# Defectoscope.net
KiCad netlist of a schematic drawn in Altium Designer
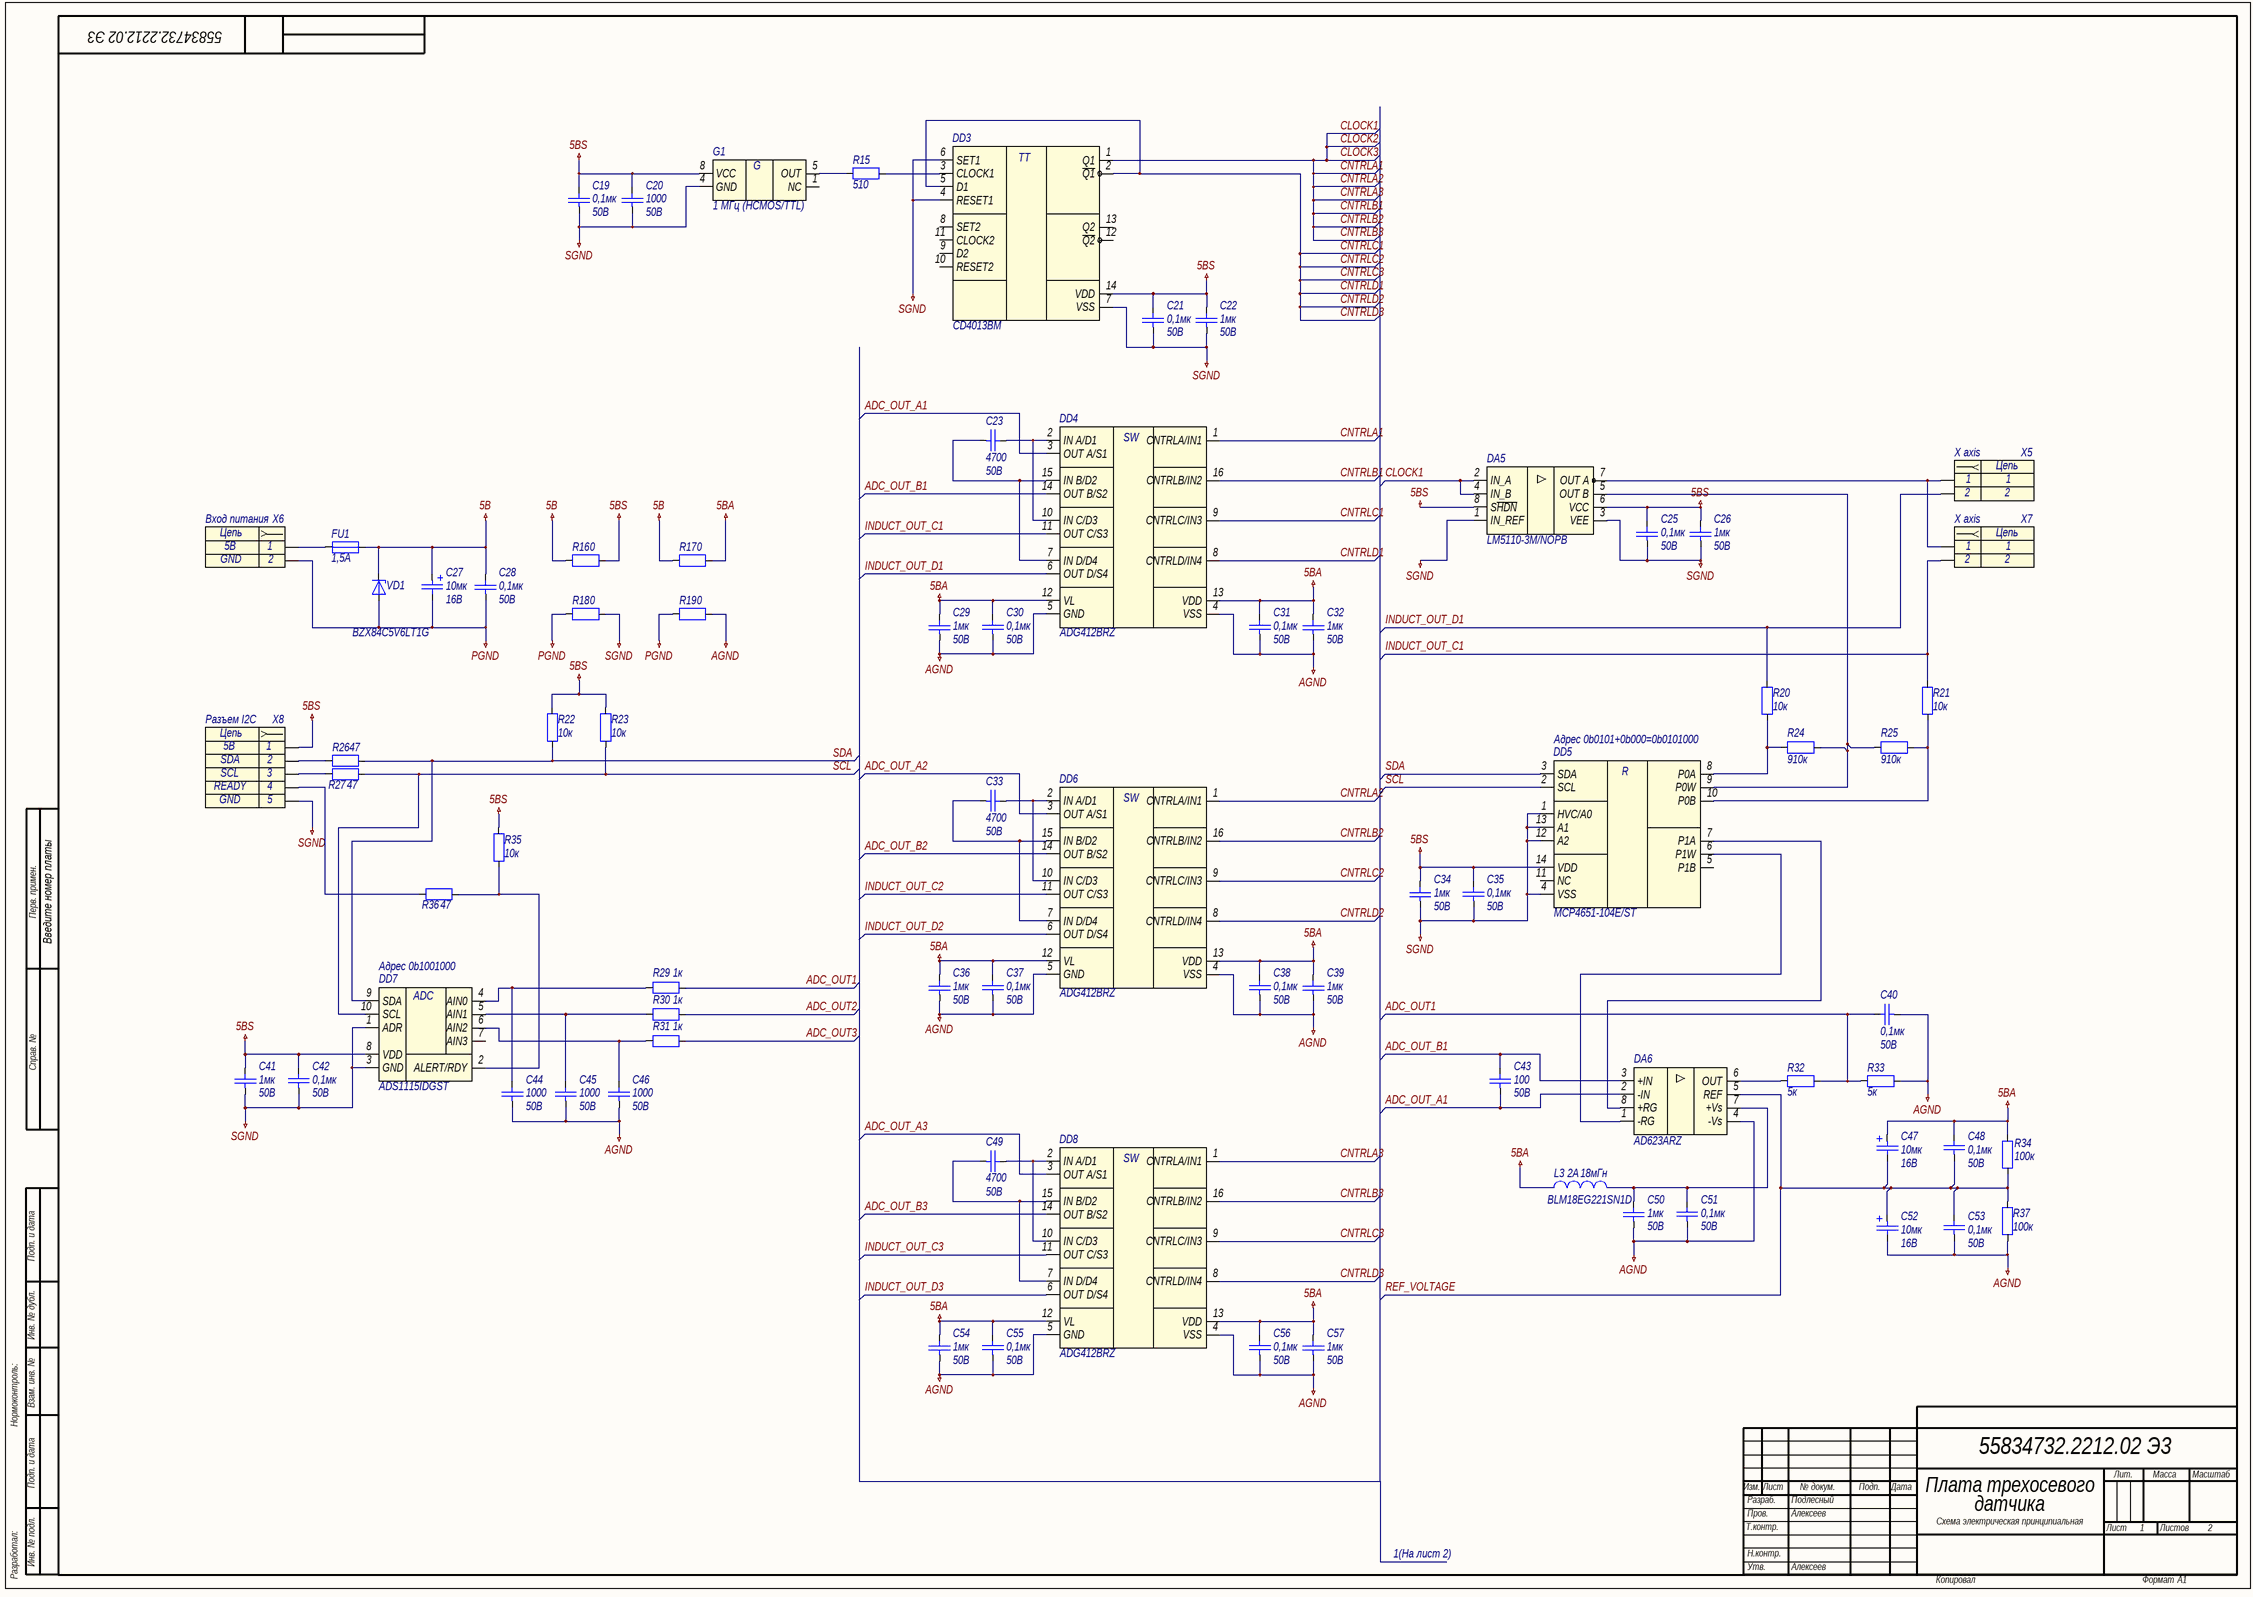
[diagram p0: Defectoscope.SchDoc]

(export (version "E")
  (design (tool "Eeschema 10.0.6"))
  (components
    (comp (ref "C19")
      (value "0,1мк")
      (footprint "ZabugorLib:C0805")
      (description "Конденсатор")
      (fields (field (name "VOLTAGE") "50В"))
      (libsource (lib "ZabugorLib") (part "Capacitor"))
    )
    (comp (ref "C20")
      (value "1000")
      (footprint "ZabugorLib:C0805")
      (description "Конденсатор")
      (fields (field (name "VOLTAGE") "50В"))
      (libsource (lib "ZabugorLib") (part "Capacitor"))
    )
    (comp (ref "C21")
      (value "0,1мк")
      (footprint "ZabugorLib:C0805")
      (description "Конденсатор")
      (fields (field (name "VOLTAGE") "50В"))
      (libsource (lib "ZabugorLib") (part "Capacitor"))
    )
    (comp (ref "C22")
      (value "1мк")
      (footprint "ZabugorLib:C0805")
      (description "Конденсатор")
      (fields (field (name "VOLTAGE") "50В"))
      (libsource (lib "ZabugorLib") (part "Capacitor"))
    )
    (comp (ref "C23")
      (value "4700")
      (footprint "ZabugorLib:C0805")
      (description "Конденсатор")
      (fields (field (name "VOLTAGE") "50В"))
      (libsource (lib "ZabugorLib") (part "Capacitor"))
    )
    (comp (ref "C25")
      (value "0,1мк")
      (footprint "ZabugorLib:C0805")
      (description "Конденсатор")
      (fields (field (name "VOLTAGE") "50В"))
      (libsource (lib "ZabugorLib") (part "Capacitor"))
    )
    (comp (ref "C26")
      (value "1мк")
      (footprint "ZabugorLib:C0805")
      (description "Конденсатор")
      (fields (field (name "VOLTAGE") "50В"))
      (libsource (lib "ZabugorLib") (part "Capacitor"))
    )
    (comp (ref "C27")
      (value "10мк")
      (footprint "ZabugorLib:TANTAL CASE B")
      (description "Конденсатор полярный")
      (fields (field (name "VOLTAGE") "16В"))
      (libsource (lib "ZabugorLib") (part "Capacitor_pol"))
    )
    (comp (ref "C28")
      (value "0,1мк")
      (footprint "ZabugorLib:C0805")
      (description "Конденсатор")
      (fields (field (name "VOLTAGE") "50В"))
      (libsource (lib "ZabugorLib") (part "Capacitor"))
    )
    (comp (ref "C29")
      (value "1мк")
      (footprint "ZabugorLib:C0805")
      (description "Конденсатор")
      (fields (field (name "VOLTAGE") "50В"))
      (libsource (lib "ZabugorLib") (part "Capacitor"))
    )
    (comp (ref "C30")
      (value "0,1мк")
      (footprint "ZabugorLib:C0805")
      (description "Конденсатор")
      (fields (field (name "VOLTAGE") "50В"))
      (libsource (lib "ZabugorLib") (part "Capacitor"))
    )
    (comp (ref "C31")
      (value "0,1мк")
      (footprint "ZabugorLib:C0805")
      (description "Конденсатор")
      (fields (field (name "VOLTAGE") "50В"))
      (libsource (lib "ZabugorLib") (part "Capacitor"))
    )
    (comp (ref "C32")
      (value "1мк")
      (footprint "ZabugorLib:C0805")
      (description "Конденсатор")
      (fields (field (name "VOLTAGE") "50В"))
      (libsource (lib "ZabugorLib") (part "Capacitor"))
    )
    (comp (ref "C33")
      (value "4700")
      (footprint "ZabugorLib:C0805")
      (description "Конденсатор")
      (fields (field (name "VOLTAGE") "50В"))
      (libsource (lib "ZabugorLib") (part "Capacitor"))
    )
    (comp (ref "C34")
      (value "1мк")
      (footprint "ZabugorLib:C0805")
      (description "Конденсатор")
      (fields (field (name "VOLTAGE") "50В"))
      (libsource (lib "ZabugorLib") (part "Capacitor"))
    )
    (comp (ref "C35")
      (value "0,1мк")
      (footprint "ZabugorLib:C0805")
      (description "Конденсатор")
      (fields (field (name "VOLTAGE") "50В"))
      (libsource (lib "ZabugorLib") (part "Capacitor"))
    )
    (comp (ref "C36")
      (value "1мк")
      (footprint "ZabugorLib:C0805")
      (description "Конденсатор")
      (fields (field (name "VOLTAGE") "50В"))
      (libsource (lib "ZabugorLib") (part "Capacitor"))
    )
    (comp (ref "C37")
      (value "0,1мк")
      (footprint "ZabugorLib:C0805")
      (description "Конденсатор")
      (fields (field (name "VOLTAGE") "50В"))
      (libsource (lib "ZabugorLib") (part "Capacitor"))
    )
    (comp (ref "C38")
      (value "0,1мк")
      (footprint "ZabugorLib:C0805")
      (description "Конденсатор")
      (fields (field (name "VOLTAGE") "50В"))
      (libsource (lib "ZabugorLib") (part "Capacitor"))
    )
    (comp (ref "C39")
      (value "1мк")
      (footprint "ZabugorLib:C0805")
      (description "Конденсатор")
      (fields (field (name "VOLTAGE") "50В"))
      (libsource (lib "ZabugorLib") (part "Capacitor"))
    )
    (comp (ref "C40")
      (value "0,1мк")
      (footprint "ZabugorLib:C0805")
      (description "Конденсатор")
      (fields (field (name "VOLTAGE") "50В"))
      (libsource (lib "ZabugorLib") (part "Capacitor"))
    )
    (comp (ref "C41")
      (value "1мк")
      (footprint "ZabugorLib:C0805")
      (description "Конденсатор")
      (fields (field (name "VOLTAGE") "50В"))
      (libsource (lib "ZabugorLib") (part "Capacitor"))
    )
    (comp (ref "C42")
      (value "0,1мк")
      (footprint "ZabugorLib:C0805")
      (description "Конденсатор")
      (fields (field (name "VOLTAGE") "50В"))
      (libsource (lib "ZabugorLib") (part "Capacitor"))
    )
    (comp (ref "C43")
      (value "100")
      (footprint "ZabugorLib:C0805")
      (description "Конденсатор")
      (fields (field (name "VOLTAGE") "50В"))
      (libsource (lib "ZabugorLib") (part "Capacitor"))
    )
    (comp (ref "C44")
      (value "1000")
      (footprint "ZabugorLib:C0805")
      (description "Конденсатор")
      (fields (field (name "VOLTAGE") "50В"))
      (libsource (lib "ZabugorLib") (part "Capacitor"))
    )
    (comp (ref "C45")
      (value "1000")
      (footprint "ZabugorLib:C0805")
      (description "Конденсатор")
      (fields (field (name "VOLTAGE") "50В"))
      (libsource (lib "ZabugorLib") (part "Capacitor"))
    )
    (comp (ref "C46")
      (value "1000")
      (footprint "ZabugorLib:C0805")
      (description "Конденсатор")
      (fields (field (name "VOLTAGE") "50В"))
      (libsource (lib "ZabugorLib") (part "Capacitor"))
    )
    (comp (ref "C47")
      (value "10мк")
      (footprint "ZabugorLib:TANTAL CASE B")
      (description "Конденсатор полярный")
      (fields (field (name "VOLTAGE") "16В"))
      (libsource (lib "ZabugorLib") (part "Capacitor_pol"))
    )
    (comp (ref "C48")
      (value "0,1мк")
      (footprint "ZabugorLib:C0805")
      (description "Конденсатор")
      (fields (field (name "VOLTAGE") "50В"))
      (libsource (lib "ZabugorLib") (part "Capacitor"))
    )
    (comp (ref "C49")
      (value "4700")
      (footprint "ZabugorLib:C0805")
      (description "Конденсатор")
      (fields (field (name "VOLTAGE") "50В"))
      (libsource (lib "ZabugorLib") (part "Capacitor"))
    )
    (comp (ref "C50")
      (value "1мк")
      (footprint "ZabugorLib:C0805")
      (description "Конденсатор")
      (fields (field (name "VOLTAGE") "50В"))
      (libsource (lib "ZabugorLib") (part "Capacitor"))
    )
    (comp (ref "C51")
      (value "0,1мк")
      (footprint "ZabugorLib:C0805")
      (description "Конденсатор")
      (fields (field (name "VOLTAGE") "50В"))
      (libsource (lib "ZabugorLib") (part "Capacitor"))
    )
    (comp (ref "C52")
      (value "10мк")
      (footprint "ZabugorLib:TANTAL CASE B")
      (description "Конденсатор полярный")
      (fields (field (name "VOLTAGE") "16В"))
      (libsource (lib "ZabugorLib") (part "Capacitor_pol"))
    )
    (comp (ref "C53")
      (value "0,1мк")
      (footprint "ZabugorLib:C0805")
      (description "Конденсатор")
      (fields (field (name "VOLTAGE") "50В"))
      (libsource (lib "ZabugorLib") (part "Capacitor"))
    )
    (comp (ref "C54")
      (value "1мк")
      (footprint "ZabugorLib:C0805")
      (description "Конденсатор")
      (fields (field (name "VOLTAGE") "50В"))
      (libsource (lib "ZabugorLib") (part "Capacitor"))
    )
    (comp (ref "C55")
      (value "0,1мк")
      (footprint "ZabugorLib:C0805")
      (description "Конденсатор")
      (fields (field (name "VOLTAGE") "50В"))
      (libsource (lib "ZabugorLib") (part "Capacitor"))
    )
    (comp (ref "C56")
      (value "0,1мк")
      (footprint "ZabugorLib:C0805")
      (description "Конденсатор")
      (fields (field (name "VOLTAGE") "50В"))
      (libsource (lib "ZabugorLib") (part "Capacitor"))
    )
    (comp (ref "C57")
      (value "1мк")
      (footprint "ZabugorLib:C0805")
      (description "Конденсатор")
      (fields (field (name "VOLTAGE") "50В"))
      (libsource (lib "ZabugorLib") (part "Capacitor"))
    )
    (comp (ref "DA5")
      (value "LM5110-3M/NOPB")
      (footprint "ZabugorLib:SO8")
      (description "Драйвер затвора")
      (libsource (lib "ZabugorLib") (part "LM5110"))
    )
    (comp (ref "DA6")
      (value "AD623ARZ")
      (footprint "ZabugorLib:SO8")
      (description "Инструментальный усилитель ±6В")
      (libsource (lib "ZabugorLib") (part "AD623ARZ"))
    )
    (comp (ref "DD3")
      (value "CD4013BM")
      (footprint "ZabugorLib:SO14")
      (description "CMOS Dual D-Type Flip-Flop")
      (libsource (lib "ZabugorLib") (part "CD4013B"))
    )
    (comp (ref "DD4")
      (value "ADG412BRZ")
      (footprint "ZabugorLib:SO-16")
      (description "CMOS Bilateral Switch")
      (libsource (lib "ZabugorLib") (part "ADG412BRZ"))
    )
    (comp (ref "DD5")
      (value "MCP4651-104E/ST")
      (footprint "ZabugorLib:TSSOP14")
      (description "Dual I2C Digital Potentiometer")
      (libsource (lib "ZabugorLib") (part "MCP4651-103"))
    )
    (comp (ref "DD6")
      (value "ADG412BRZ")
      (footprint "ZabugorLib:SO-16")
      (description "CMOS Bilateral Switch")
      (libsource (lib "ZabugorLib") (part "ADG412BRZ"))
    )
    (comp (ref "DD7")
      (value "ADS1115IDGST")
      (footprint "ZabugorLib:MSOP-10")
      (description "Ultra-Small, Low-Power, 16-Bit  Analog-to-Digital Converter with Internal Reference")
      (libsource (lib "ZabugorLib") (part "ADS1115"))
    )
    (comp (ref "DD8")
      (value "ADG412BRZ")
      (footprint "ZabugorLib:SO-16")
      (description "CMOS Bilateral Switch")
      (libsource (lib "ZabugorLib") (part "ADG412BRZ"))
    )
    (comp (ref "FU1")
      (value "1,5A")
      (footprint "ZabugorLib:FUSE812")
      (description "Предохранитель")
      (fields (field (name "Comment") "MF-MSMF150"))
      (libsource (lib "ZabugorLib") (part "Fuse"))
    )
    (comp (ref "G1")
      (value "1 МГц (HCMOS/TTL)")
      (footprint "ZabugorLib:DIL8")
      (description "Кварцевый генератор")
      (libsource (lib "ZabugorLib") (part "Crystal Oscillator DIP"))
    )
    (comp (ref "L3")
      (value "18мГн")
      (footprint "ZabugorLib:L0603")
      (description "Катушка индуктивности")
      (fields (field (name "NAME") "BLM18EG221SN1D") (field (name "IMAX") "2А"))
      (libsource (lib "ZabugorLib") (part "Inductor"))
    )
    (comp (ref "R15")
      (value "510")
      (footprint "ZabugorLib:R0805")
      (description "Резистор")
      (libsource (lib "") (part "Resistor_1"))
    )
    (comp (ref "R16")
      (value "0")
      (footprint "ZabugorLib:R0805")
      (description "Резистор")
      (libsource (lib "") (part "Resistor_1"))
    )
    (comp (ref "R17")
      (value "0")
      (footprint "ZabugorLib:R0805")
      (description "Резистор")
      (libsource (lib "") (part "Resistor_1"))
    )
    (comp (ref "R18")
      (value "0")
      (footprint "ZabugorLib:R0805")
      (description "Резистор")
      (libsource (lib "") (part "Resistor_1"))
    )
    (comp (ref "R19")
      (value "0")
      (footprint "ZabugorLib:R0805")
      (description "Резистор")
      (libsource (lib "") (part "Resistor_1"))
    )
    (comp (ref "R20")
      (value "10к")
      (footprint "ZabugorLib:R0805")
      (description "Резистор")
      (libsource (lib "") (part "Resistor_2"))
    )
    (comp (ref "R21")
      (value "10к")
      (footprint "ZabugorLib:R0805")
      (description "Резистор")
      (libsource (lib "") (part "Resistor_2"))
    )
    (comp (ref "R22")
      (value "10к")
      (footprint "ZabugorLib:R0805")
      (description "Резистор")
      (libsource (lib "") (part "Resistor_3"))
    )
    (comp (ref "R23")
      (value "10к")
      (footprint "ZabugorLib:R0805")
      (description "Резистор")
      (libsource (lib "") (part "Resistor_3"))
    )
    (comp (ref "R24")
      (value "910к")
      (footprint "ZabugorLib:R0805")
      (description "Резистор")
      (libsource (lib "ZabugorLib") (part "Resistor"))
    )
    (comp (ref "R25")
      (value "910к")
      (footprint "ZabugorLib:R0805")
      (description "Резистор")
      (libsource (lib "ZabugorLib") (part "Resistor"))
    )
    (comp (ref "R26")
      (value "47")
      (footprint "ZabugorLib:R0805")
      (description "Резистор")
      (libsource (lib "") (part "Resistor_1"))
    )
    (comp (ref "R27")
      (value "47")
      (footprint "ZabugorLib:R0805")
      (description "Резистор")
      (libsource (lib "") (part "Resistor_1"))
    )
    (comp (ref "R29")
      (value "1к")
      (footprint "ZabugorLib:R0805")
      (description "Резистор")
      (libsource (lib "ZabugorLib") (part "Resistor"))
    )
    (comp (ref "R30")
      (value "1к")
      (footprint "ZabugorLib:R0805")
      (description "Резистор")
      (libsource (lib "ZabugorLib") (part "Resistor"))
    )
    (comp (ref "R31")
      (value "1к")
      (footprint "ZabugorLib:R0805")
      (description "Резистор")
      (libsource (lib "ZabugorLib") (part "Resistor"))
    )
    (comp (ref "R32")
      (value "5к")
      (footprint "ZabugorLib:R0805")
      (description "Резистор")
      (libsource (lib "") (part "Resistor_1"))
    )
    (comp (ref "R33")
      (value "5к")
      (footprint "ZabugorLib:R0805")
      (description "Резистор")
      (libsource (lib "") (part "Resistor_1"))
    )
    (comp (ref "R34")
      (value "100к")
      (footprint "ZabugorLib:R0805")
      (description "Резистор")
      (libsource (lib "ZabugorLib") (part "Resistor"))
    )
    (comp (ref "R35")
      (value "10к")
      (footprint "ZabugorLib:R0805")
      (description "Резистор")
      (libsource (lib "") (part "Resistor_3"))
    )
    (comp (ref "R36")
      (value "47")
      (footprint "ZabugorLib:R0805")
      (description "Резистор")
      (libsource (lib "") (part "Resistor_1"))
    )
    (comp (ref "R37")
      (value "100к")
      (footprint "ZabugorLib:R0805")
      (description "Резистор")
      (libsource (lib "ZabugorLib") (part "Resistor"))
    )
    (comp (ref "VD1")
      (value "BZX84C5V6LT1G")
      (footprint "ZabugorLib:SOT23-3")
      (description "Стабилитрон")
      (fields (field (name "NAME") "BZX84C5V6LT1G"))
      (libsource (lib "ZabugorLib") (part "DiodeZener"))
    )
    (comp (ref "X5")
      (value "X axis")
      (footprint "ZabugorLib:MW-2M")
      (description "Разъем - 2 конт. розетка")
      (libsource (lib "ZabugorLib") (part "Header_2_sct"))
    )
    (comp (ref "X6")
      (value "Вход питания")
      (footprint "ZabugorLib:MW-2M")
      (description "Разъем - 2 конт. розетка")
      (libsource (lib "") (part "Header_2_sct_1"))
    )
    (comp (ref "X7")
      (value "X axis")
      (footprint "ZabugorLib:MW-2M")
      (description "Разъем - 2 конт. розетка")
      (libsource (lib "ZabugorLib") (part "Header_2_sct"))
    )
    (comp (ref "X8")
      (value "Разъем I2C")
      (footprint "ZabugorLib:MW-5M")
      (description "Разъем - 4 конт. розетка")
      (libsource (lib "ZabugorLib") (part "Header_5_sct"))
    )
  )
  (nets
    (net (code "1") (name "/ADC_OUT1") (class "Default")
      (node (ref "C40") (pin "2") (pinfunction "2_2") (pintype "passive"))
      (node (ref "R29") (pin "2") (pinfunction "2_2") (pintype "passive"))
      (node (ref "R32") (pin "1") (pinfunction "1_1") (pintype "passive"))
      (node (ref "R33") (pin "2") (pinfunction "2_2") (pintype "passive"))
    )
    (net (code "2") (name "/ADC_OUT2") (class "Default")
      (node (ref "R30") (pin "2") (pinfunction "2_2") (pintype "passive"))
    )
    (net (code "3") (name "/ADC_OUT3") (class "Default")
      (node (ref "R31") (pin "2") (pinfunction "2_2") (pintype "passive"))
    )
    (net (code "4") (name "/ADC_OUT_A1") (class "Default")
      (node (ref "C43") (pin "1") (pinfunction "1_1") (pintype "passive"))
      (node (ref "DA6") (pin "2") (pinfunction "-IN_2") (pintype "passive"))
      (node (ref "DD4") (pin "3") (pinfunction "OUT_A/S1_3") (pintype "power_in"))
    )
    (net (code "5") (name "/ADC_OUT_A2") (class "Default")
      (node (ref "DD6") (pin "3") (pinfunction "OUT_A/S1_3") (pintype "power_in"))
    )
    (net (code "6") (name "/ADC_OUT_A3") (class "Default")
      (node (ref "DD8") (pin "3") (pinfunction "OUT_A/S1_3") (pintype "power_in"))
    )
    (net (code "7") (name "/ADC_OUT_B1") (class "Default")
      (node (ref "C43") (pin "2") (pinfunction "2_2") (pintype "passive"))
      (node (ref "DA6") (pin "3") (pinfunction "+IN_3") (pintype "passive"))
      (node (ref "DD4") (pin "14") (pinfunction "OUT_B/S2_14") (pintype "power_in"))
    )
    (net (code "8") (name "/ADC_OUT_B2") (class "Default")
      (node (ref "DD6") (pin "14") (pinfunction "OUT_B/S2_14") (pintype "power_in"))
    )
    (net (code "9") (name "/ADC_OUT_B3") (class "Default")
      (node (ref "DD8") (pin "14") (pinfunction "OUT_B/S2_14") (pintype "power_in"))
    )
    (net (code "10") (name "/CLOCK1") (class "Default")
      (node (ref "DA5") (pin "2") (pinfunction "IN_A_2") (pintype "passive"))
      (node (ref "DA5") (pin "4") (pinfunction "IN_B_4") (pintype "passive"))
      (node (ref "DD3") (pin "1") (pinfunction "Q1_1") (pintype "power_in"))
      (node (ref "DD4") (pin "1") (pinfunction "CNTRLA/IN1_1") (pintype "power_in"))
      (node (ref "DD4") (pin "16") (pinfunction "CNTRLB/IN2_16") (pintype "power_in"))
      (node (ref "DD6") (pin "1") (pinfunction "CNTRLA/IN1_1") (pintype "power_in"))
      (node (ref "DD6") (pin "16") (pinfunction "CNTRLB/IN2_16") (pintype "power_in"))
      (node (ref "DD8") (pin "1") (pinfunction "CNTRLA/IN1_1") (pintype "power_in"))
      (node (ref "DD8") (pin "16") (pinfunction "CNTRLB/IN2_16") (pintype "power_in"))
    )
    (net (code "11") (name "/CNTRLC1") (class "Default")
      (node (ref "DD3") (pin "2") (pinfunction "~{Q1}_2") (pintype "power_in"))
      (node (ref "DD3") (pin "5") (pinfunction "D1_5") (pintype "power_in"))
      (node (ref "DD4") (pin "8") (pinfunction "CNTRLD/IN4_8") (pintype "power_in"))
      (node (ref "DD4") (pin "9") (pinfunction "CNTRLC/IN3_9") (pintype "power_in"))
      (node (ref "DD6") (pin "8") (pinfunction "CNTRLD/IN4_8") (pintype "power_in"))
      (node (ref "DD6") (pin "9") (pinfunction "CNTRLC/IN3_9") (pintype "power_in"))
      (node (ref "DD8") (pin "8") (pinfunction "CNTRLD/IN4_8") (pintype "power_in"))
      (node (ref "DD8") (pin "9") (pinfunction "CNTRLC/IN3_9") (pintype "power_in"))
    )
    (net (code "12") (name "/INDUCT_OUT_C1") (class "Default")
      (node (ref "DD4") (pin "11") (pinfunction "OUT_C/S3_11") (pintype "power_in"))
      (node (ref "R21") (pin "1") (pinfunction "1_1") (pintype "passive"))
      (node (ref "X7") (pin "2") (pinfunction "2_2") (pintype "passive"))
    )
    (net (code "13") (name "/INDUCT_OUT_C2") (class "Default")
      (node (ref "DD6") (pin "11") (pinfunction "OUT_C/S3_11") (pintype "power_in"))
    )
    (net (code "14") (name "/INDUCT_OUT_C3") (class "Default")
      (node (ref "DD8") (pin "11") (pinfunction "OUT_C/S3_11") (pintype "power_in"))
    )
    (net (code "15") (name "/INDUCT_OUT_D1") (class "Default")
      (node (ref "DD4") (pin "6") (pinfunction "OUT_D/S4_6") (pintype "power_in"))
      (node (ref "R20") (pin "1") (pinfunction "1_1") (pintype "passive"))
      (node (ref "X5") (pin "2") (pinfunction "2_2") (pintype "passive"))
    )
    (net (code "16") (name "/INDUCT_OUT_D2") (class "Default")
      (node (ref "DD6") (pin "6") (pinfunction "OUT_D/S4_6") (pintype "power_in"))
    )
    (net (code "17") (name "/INDUCT_OUT_D3") (class "Default")
      (node (ref "DD8") (pin "6") (pinfunction "OUT_D/S4_6") (pintype "power_in"))
    )
    (net (code "18") (name "/REF_VOLTAGE") (class "Default")
      (node (ref "C47") (pin "2") (pinfunction "2_2") (pintype "passive"))
      (node (ref "C48") (pin "1") (pinfunction "1_1") (pintype "passive"))
      (node (ref "C52") (pin "1") (pinfunction "1_1") (pintype "passive"))
      (node (ref "C53") (pin "2") (pinfunction "2_2") (pintype "passive"))
      (node (ref "DA6") (pin "5") (pinfunction "REF_5") (pintype "passive"))
      (node (ref "R34") (pin "1") (pinfunction "1_1") (pintype "passive"))
      (node (ref "R37") (pin "2") (pinfunction "2_2") (pintype "passive"))
    )
    (net (code "19") (name "/SCL") (class "Default")
      (node (ref "DD5") (pin "2") (pinfunction "SCL_2") (pintype "power_in"))
      (node (ref "DD7") (pin "10") (pinfunction "SCL_10") (pintype "power_in"))
      (node (ref "R23") (pin "1") (pinfunction "1_1") (pintype "passive"))
      (node (ref "R27") (pin "1") (pinfunction "1_1") (pintype "passive"))
    )
    (net (code "20") (name "/SDA") (class "Default")
      (node (ref "DD5") (pin "3") (pinfunction "SDA_3") (pintype "power_in"))
      (node (ref "DD7") (pin "9") (pinfunction "SDA_9") (pintype "power_in"))
      (node (ref "R22") (pin "1") (pinfunction "1_1") (pintype "passive"))
      (node (ref "R26") (pin "1") (pinfunction "1_1") (pintype "passive"))
    )
    (net (code "21") (name "5B") (class "Default")
      (node (ref "C27") (pin "1") (pinfunction "1_1") (pintype "passive"))
      (node (ref "C28") (pin "2") (pinfunction "2_2") (pintype "passive"))
      (node (ref "FU1") (pin "2") (pinfunction "2_2") (pintype "passive"))
      (node (ref "R16") (pin "2") (pinfunction "2_2") (pintype "passive"))
      (node (ref "R17") (pin "2") (pinfunction "2_2") (pintype "passive"))
      (node (ref "VD1") (pin "1") (pinfunction "K_1") (pintype "passive"))
    )
    (net (code "22") (name "5BA") (class "Default")
      (node (ref "C29") (pin "2") (pinfunction "2_2") (pintype "passive"))
      (node (ref "C30") (pin "2") (pinfunction "2_2") (pintype "passive"))
      (node (ref "C31") (pin "2") (pinfunction "2_2") (pintype "passive"))
      (node (ref "C32") (pin "2") (pinfunction "2_2") (pintype "passive"))
      (node (ref "C36") (pin "2") (pinfunction "2_2") (pintype "passive"))
      (node (ref "C37") (pin "2") (pinfunction "2_2") (pintype "passive"))
      (node (ref "C38") (pin "2") (pinfunction "2_2") (pintype "passive"))
      (node (ref "C39") (pin "2") (pinfunction "2_2") (pintype "passive"))
      (node (ref "C47") (pin "1") (pinfunction "1_1") (pintype "passive"))
      (node (ref "C48") (pin "2") (pinfunction "2_2") (pintype "passive"))
      (node (ref "C54") (pin "2") (pinfunction "2_2") (pintype "passive"))
      (node (ref "C55") (pin "2") (pinfunction "2_2") (pintype "passive"))
      (node (ref "C56") (pin "2") (pinfunction "2_2") (pintype "passive"))
      (node (ref "C57") (pin "2") (pinfunction "2_2") (pintype "passive"))
      (node (ref "DD4") (pin "12") (pinfunction "VL_12") (pintype "power_in"))
      (node (ref "DD4") (pin "13") (pinfunction "VDD_13") (pintype "power_in"))
      (node (ref "DD6") (pin "12") (pinfunction "VL_12") (pintype "power_in"))
      (node (ref "DD6") (pin "13") (pinfunction "VDD_13") (pintype "power_in"))
      (node (ref "DD8") (pin "12") (pinfunction "VL_12") (pintype "power_in"))
      (node (ref "DD8") (pin "13") (pinfunction "VDD_13") (pintype "power_in"))
      (node (ref "L3") (pin "1") (pinfunction "1_1") (pintype "passive"))
      (node (ref "R17") (pin "1") (pinfunction "1_1") (pintype "passive"))
      (node (ref "R34") (pin "2") (pinfunction "2_2") (pintype "passive"))
    )
    (net (code "23") (name "5BS") (class "Default")
      (node (ref "C19") (pin "2") (pinfunction "2_2") (pintype "passive"))
      (node (ref "C20") (pin "2") (pinfunction "2_2") (pintype "passive"))
      (node (ref "C21") (pin "2") (pinfunction "2_2") (pintype "passive"))
      (node (ref "C22") (pin "2") (pinfunction "2_2") (pintype "passive"))
      (node (ref "C25") (pin "2") (pinfunction "2_2") (pintype "passive"))
      (node (ref "C26") (pin "2") (pinfunction "2_2") (pintype "passive"))
      (node (ref "C34") (pin "2") (pinfunction "2_2") (pintype "passive"))
      (node (ref "C35") (pin "2") (pinfunction "2_2") (pintype "passive"))
      (node (ref "C41") (pin "2") (pinfunction "2_2") (pintype "passive"))
      (node (ref "C42") (pin "2") (pinfunction "2_2") (pintype "passive"))
      (node (ref "DA5") (pin "6") (pinfunction "VCC_6") (pintype "passive"))
      (node (ref "DA5") (pin "8") (pinfunction "S~{HDN}_8") (pintype "passive"))
      (node (ref "DD3") (pin "14") (pinfunction "VDD_14") (pintype "power_in"))
      (node (ref "DD5") (pin "14") (pinfunction "VDD_14") (pintype "power_in"))
      (node (ref "DD7") (pin "8") (pinfunction "VDD_8") (pintype "power_in"))
      (node (ref "G1") (pin "8") (pinfunction "VCC_8") (pintype "power_in"))
      (node (ref "R16") (pin "1") (pinfunction "1_1") (pintype "passive"))
      (node (ref "R22") (pin "2") (pinfunction "2_2") (pintype "passive"))
      (node (ref "R23") (pin "2") (pinfunction "2_2") (pintype "passive"))
      (node (ref "R35") (pin "2") (pinfunction "2_2") (pintype "passive"))
      (node (ref "X8") (pin "1") (pinfunction "1_1") (pintype "passive"))
    )
    (net (code "24") (name "AGND") (class "Default")
      (node (ref "C29") (pin "1") (pinfunction "1_1") (pintype "passive"))
      (node (ref "C30") (pin "1") (pinfunction "1_1") (pintype "passive"))
      (node (ref "C31") (pin "1") (pinfunction "1_1") (pintype "passive"))
      (node (ref "C32") (pin "1") (pinfunction "1_1") (pintype "passive"))
      (node (ref "C36") (pin "1") (pinfunction "1_1") (pintype "passive"))
      (node (ref "C37") (pin "1") (pinfunction "1_1") (pintype "passive"))
      (node (ref "C38") (pin "1") (pinfunction "1_1") (pintype "passive"))
      (node (ref "C39") (pin "1") (pinfunction "1_1") (pintype "passive"))
      (node (ref "C40") (pin "1") (pinfunction "1_1") (pintype "passive"))
      (node (ref "C44") (pin "1") (pinfunction "1_1") (pintype "passive"))
      (node (ref "C45") (pin "1") (pinfunction "1_1") (pintype "passive"))
      (node (ref "C46") (pin "1") (pinfunction "1_1") (pintype "passive"))
      (node (ref "C50") (pin "1") (pinfunction "1_1") (pintype "passive"))
      (node (ref "C51") (pin "1") (pinfunction "1_1") (pintype "passive"))
      (node (ref "C52") (pin "2") (pinfunction "2_2") (pintype "passive"))
      (node (ref "C53") (pin "1") (pinfunction "1_1") (pintype "passive"))
      (node (ref "C54") (pin "1") (pinfunction "1_1") (pintype "passive"))
      (node (ref "C55") (pin "1") (pinfunction "1_1") (pintype "passive"))
      (node (ref "C56") (pin "1") (pinfunction "1_1") (pintype "passive"))
      (node (ref "C57") (pin "1") (pinfunction "1_1") (pintype "passive"))
      (node (ref "DA6") (pin "4") (pinfunction "-Vs_4") (pintype "passive"))
      (node (ref "DD4") (pin "4") (pinfunction "VSS_4") (pintype "power_in"))
      (node (ref "DD4") (pin "5") (pinfunction "GND_5") (pintype "power_in"))
      (node (ref "DD6") (pin "4") (pinfunction "VSS_4") (pintype "power_in"))
      (node (ref "DD6") (pin "5") (pinfunction "GND_5") (pintype "power_in"))
      (node (ref "DD8") (pin "4") (pinfunction "VSS_4") (pintype "power_in"))
      (node (ref "DD8") (pin "5") (pinfunction "GND_5") (pintype "power_in"))
      (node (ref "R19") (pin "1") (pinfunction "1_1") (pintype "passive"))
      (node (ref "R33") (pin "1") (pinfunction "1_1") (pintype "passive"))
      (node (ref "R37") (pin "1") (pinfunction "1_1") (pintype "passive"))
    )
    (net (code "25") (name "Net-(DA5-OUT_A)") (class "Default")
      (node (ref "DA5") (pin "7") (pinfunction "OUT_A_7") (pintype "passive"))
      (node (ref "X5") (pin "1") (pinfunction "1_1") (pintype "passive"))
      (node (ref "X7") (pin "1") (pinfunction "1_1") (pintype "passive"))
    )
    (net (code "26") (name "Net-(DA5-OUT_B)") (class "Default")
      (node (ref "DA5") (pin "5") (pinfunction "OUT_B_5") (pintype "passive"))
      (node (ref "DD5") (pin "9") (pinfunction "P0W_9") (pintype "power_in"))
      (node (ref "R24") (pin "2") (pinfunction "2_2") (pintype "passive"))
      (node (ref "R25") (pin "1") (pinfunction "1_1") (pintype "passive"))
    )
    (net (code "27") (name "Net-(DA6-+RG)") (class "Default")
      (node (ref "DA6") (pin "8") (pinfunction "+RG_8") (pintype "passive"))
      (node (ref "DD5") (pin "7") (pinfunction "P1A_7") (pintype "power_in"))
    )
    (net (code "28") (name "Net-(DA6-+Vs)") (class "Default")
      (node (ref "C50") (pin "2") (pinfunction "2_2") (pintype "passive"))
      (node (ref "C51") (pin "2") (pinfunction "2_2") (pintype "passive"))
      (node (ref "DA6") (pin "7") (pinfunction "+Vs_7") (pintype "passive"))
      (node (ref "L3") (pin "2") (pinfunction "2_2") (pintype "passive"))
    )
    (net (code "29") (name "Net-(DA6--RG)") (class "Default")
      (node (ref "DA6") (pin "1") (pinfunction "-RG_1") (pintype "passive"))
      (node (ref "DD5") (pin "6") (pinfunction "P1W_6") (pintype "power_in"))
    )
    (net (code "30") (name "Net-(DA6-OUT)") (class "Default")
      (node (ref "DA6") (pin "6") (pinfunction "OUT_6") (pintype "passive"))
      (node (ref "R32") (pin "2") (pinfunction "2_2") (pintype "passive"))
    )
    (net (code "31") (name "Net-(DD3-CLOCK1)") (class "Default")
      (node (ref "DD3") (pin "3") (pinfunction "CLOCK1_3") (pintype "power_in"))
      (node (ref "R15") (pin "1") (pinfunction "1_1") (pintype "passive"))
    )
    (net (code "32") (name "Net-(DD4-IN_A{slash}D1)") (class "Default")
      (node (ref "C23") (pin "2") (pinfunction "2_2") (pintype "passive"))
      (node (ref "DD4") (pin "10") (pinfunction "IN_C/D3_10") (pintype "power_in"))
      (node (ref "DD4") (pin "2") (pinfunction "IN_A/D1_2") (pintype "power_in"))
    )
    (net (code "33") (name "Net-(DD4-IN_B{slash}D2)") (class "Default")
      (node (ref "C23") (pin "1") (pinfunction "1_1") (pintype "passive"))
      (node (ref "DD4") (pin "15") (pinfunction "IN_B/D2_15") (pintype "power_in"))
      (node (ref "DD4") (pin "7") (pinfunction "IN_D/D4_7") (pintype "power_in"))
    )
    (net (code "34") (name "Net-(DD5-P0A)") (class "Default")
      (node (ref "DD5") (pin "8") (pinfunction "P0A_8") (pintype "power_in"))
      (node (ref "R20") (pin "2") (pinfunction "2_2") (pintype "passive"))
      (node (ref "R24") (pin "1") (pinfunction "1_1") (pintype "passive"))
    )
    (net (code "35") (name "Net-(DD5-P0B)") (class "Default")
      (node (ref "DD5") (pin "10") (pinfunction "P0B_10") (pintype "power_in"))
      (node (ref "R21") (pin "2") (pinfunction "2_2") (pintype "passive"))
      (node (ref "R25") (pin "2") (pinfunction "2_2") (pintype "passive"))
    )
    (net (code "36") (name "Net-(DD6-IN_A{slash}D1)") (class "Default")
      (node (ref "C33") (pin "2") (pinfunction "2_2") (pintype "passive"))
      (node (ref "DD6") (pin "10") (pinfunction "IN_C/D3_10") (pintype "power_in"))
      (node (ref "DD6") (pin "2") (pinfunction "IN_A/D1_2") (pintype "power_in"))
    )
    (net (code "37") (name "Net-(DD6-IN_B{slash}D2)") (class "Default")
      (node (ref "C33") (pin "1") (pinfunction "1_1") (pintype "passive"))
      (node (ref "DD6") (pin "15") (pinfunction "IN_B/D2_15") (pintype "power_in"))
      (node (ref "DD6") (pin "7") (pinfunction "IN_D/D4_7") (pintype "power_in"))
    )
    (net (code "38") (name "Net-(DD7-AIN0)") (class "Default")
      (node (ref "C44") (pin "2") (pinfunction "2_2") (pintype "passive"))
      (node (ref "DD7") (pin "4") (pinfunction "AIN0_4") (pintype "power_in"))
      (node (ref "R29") (pin "1") (pinfunction "1_1") (pintype "passive"))
    )
    (net (code "39") (name "Net-(DD7-AIN1)") (class "Default")
      (node (ref "C45") (pin "2") (pinfunction "2_2") (pintype "passive"))
      (node (ref "DD7") (pin "5") (pinfunction "AIN1_5") (pintype "power_in"))
      (node (ref "R30") (pin "1") (pinfunction "1_1") (pintype "passive"))
    )
    (net (code "40") (name "Net-(DD7-AIN2)") (class "Default")
      (node (ref "C46") (pin "2") (pinfunction "2_2") (pintype "passive"))
      (node (ref "DD7") (pin "6") (pinfunction "AIN2_6") (pintype "power_in"))
      (node (ref "R31") (pin "1") (pinfunction "1_1") (pintype "passive"))
    )
    (net (code "41") (name "Net-(DD7-ALERT{slash}RDY)") (class "Default")
      (node (ref "DD7") (pin "2") (pinfunction "ALERT/RDY_2") (pintype "power_in"))
      (node (ref "R35") (pin "1") (pinfunction "1_1") (pintype "passive"))
      (node (ref "R36") (pin "1") (pinfunction "1_1") (pintype "passive"))
    )
    (net (code "42") (name "Net-(DD8-IN_A{slash}D1)") (class "Default")
      (node (ref "C49") (pin "2") (pinfunction "2_2") (pintype "passive"))
      (node (ref "DD8") (pin "10") (pinfunction "IN_C/D3_10") (pintype "power_in"))
      (node (ref "DD8") (pin "2") (pinfunction "IN_A/D1_2") (pintype "power_in"))
    )
    (net (code "43") (name "Net-(DD8-IN_B{slash}D2)") (class "Default")
      (node (ref "C49") (pin "1") (pinfunction "1_1") (pintype "passive"))
      (node (ref "DD8") (pin "15") (pinfunction "IN_B/D2_15") (pintype "power_in"))
      (node (ref "DD8") (pin "7") (pinfunction "IN_D/D4_7") (pintype "power_in"))
    )
    (net (code "44") (name "Net-(FU1-Pad1)") (class "Default")
      (node (ref "FU1") (pin "1") (pinfunction "1_1") (pintype "passive"))
      (node (ref "X6") (pin "1") (pinfunction "1_1") (pintype "passive"))
    )
    (net (code "45") (name "Net-(G1-OUT)") (class "Default")
      (node (ref "G1") (pin "5") (pinfunction "OUT_5") (pintype "power_in"))
      (node (ref "R15") (pin "2") (pinfunction "2_2") (pintype "passive"))
    )
    (net (code "46") (name "Net-(R26-Pad2)") (class "Default")
      (node (ref "R26") (pin "2") (pinfunction "2_2") (pintype "passive"))
      (node (ref "X8") (pin "2") (pinfunction "2_2") (pintype "passive"))
    )
    (net (code "47") (name "Net-(R27-Pad2)") (class "Default")
      (node (ref "R27") (pin "2") (pinfunction "2_2") (pintype "passive"))
      (node (ref "X8") (pin "3") (pinfunction "3_3") (pintype "passive"))
    )
    (net (code "48") (name "Net-(R36-Pad2)") (class "Default")
      (node (ref "R36") (pin "2") (pinfunction "2_2") (pintype "passive"))
      (node (ref "X8") (pin "4") (pinfunction "4_4") (pintype "passive"))
    )
    (net (code "49") (name "PGND") (class "Default")
      (node (ref "C27") (pin "2") (pinfunction "2_2") (pintype "passive"))
      (node (ref "C28") (pin "1") (pinfunction "1_1") (pintype "passive"))
      (node (ref "R18") (pin "2") (pinfunction "2_2") (pintype "passive"))
      (node (ref "R19") (pin "2") (pinfunction "2_2") (pintype "passive"))
      (node (ref "VD1") (pin "2") (pinfunction "A_2") (pintype "passive"))
      (node (ref "X6") (pin "2") (pinfunction "2_2") (pintype "passive"))
    )
    (net (code "50") (name "SGND") (class "Default")
      (node (ref "C19") (pin "1") (pinfunction "1_1") (pintype "passive"))
      (node (ref "C20") (pin "1") (pinfunction "1_1") (pintype "passive"))
      (node (ref "C21") (pin "1") (pinfunction "1_1") (pintype "passive"))
      (node (ref "C22") (pin "1") (pinfunction "1_1") (pintype "passive"))
      (node (ref "C25") (pin "1") (pinfunction "1_1") (pintype "passive"))
      (node (ref "C26") (pin "1") (pinfunction "1_1") (pintype "passive"))
      (node (ref "C34") (pin "1") (pinfunction "1_1") (pintype "passive"))
      (node (ref "C35") (pin "1") (pinfunction "1_1") (pintype "passive"))
      (node (ref "C41") (pin "1") (pinfunction "1_1") (pintype "passive"))
      (node (ref "C42") (pin "1") (pinfunction "1_1") (pintype "passive"))
      (node (ref "DA5") (pin "1") (pinfunction "IN_REF_1") (pintype "passive"))
      (node (ref "DA5") (pin "3") (pinfunction "VEE_3") (pintype "passive"))
      (node (ref "DD3") (pin "4") (pinfunction "RESET1_4") (pintype "power_in"))
      (node (ref "DD3") (pin "6") (pinfunction "SET1_6") (pintype "power_in"))
      (node (ref "DD3") (pin "7") (pinfunction "VSS_7") (pintype "power_in"))
      (node (ref "DD5") (pin "1") (pinfunction "HVC/A0_1") (pintype "power_in"))
      (node (ref "DD5") (pin "12") (pinfunction "A2_12") (pintype "power_in"))
      (node (ref "DD5") (pin "13") (pinfunction "A1_13") (pintype "power_in"))
      (node (ref "DD5") (pin "4") (pinfunction "VSS_4") (pintype "power_in"))
      (node (ref "DD7") (pin "1") (pinfunction "ADR_1") (pintype "power_in"))
      (node (ref "DD7") (pin "3") (pinfunction "GND_3") (pintype "power_in"))
      (node (ref "G1") (pin "4") (pinfunction "GND_4") (pintype "power_in"))
      (node (ref "R18") (pin "1") (pinfunction "1_1") (pintype "passive"))
      (node (ref "X8") (pin "5") (pinfunction "5_5") (pintype "passive"))
    )
    (net (code "51") (name "unconnected-(DD3-CLOCK2-Pad11)") (class "Default")
      (node (ref "DD3") (pin "11") (pinfunction "CLOCK2_11") (pintype "power_in"))
    )
    (net (code "52") (name "unconnected-(DD3-D2-Pad9)") (class "Default")
      (node (ref "DD3") (pin "9") (pinfunction "D2_9") (pintype "power_in"))
    )
    (net (code "53") (name "unconnected-(DD3-Q2-Pad13)") (class "Default")
      (node (ref "DD3") (pin "13") (pinfunction "Q2_13") (pintype "power_in"))
    )
    (net (code "54") (name "unconnected-(DD3-RESET2-Pad10)") (class "Default")
      (node (ref "DD3") (pin "10") (pinfunction "RESET2_10") (pintype "power_in"))
    )
    (net (code "55") (name "unconnected-(DD3-SET2-Pad8)") (class "Default")
      (node (ref "DD3") (pin "8") (pinfunction "SET2_8") (pintype "power_in"))
    )
    (net (code "56") (name "unconnected-(DD3-~{Q2}-Pad12)") (class "Default")
      (node (ref "DD3") (pin "12") (pinfunction "~{Q2}_12") (pintype "power_in"))
    )
    (net (code "57") (name "unconnected-(DD5-NC-Pad11)") (class "Default")
      (node (ref "DD5") (pin "11") (pinfunction "NC_11") (pintype "power_in"))
    )
    (net (code "58") (name "unconnected-(DD5-P1B-Pad5)") (class "Default")
      (node (ref "DD5") (pin "5") (pinfunction "P1B_5") (pintype "power_in"))
    )
    (net (code "59") (name "unconnected-(DD7-AIN3-Pad7)") (class "Default")
      (node (ref "DD7") (pin "7") (pinfunction "AIN3_7") (pintype "power_in"))
    )
    (net (code "60") (name "unconnected-(G1-NC-Pad1)") (class "Default")
      (node (ref "G1") (pin "1") (pinfunction "NC_1") (pintype "power_in"))
    )
  )
)
